# neopixel_studio_light.net
KiCad netlist of a schematic drawn in EAGLE
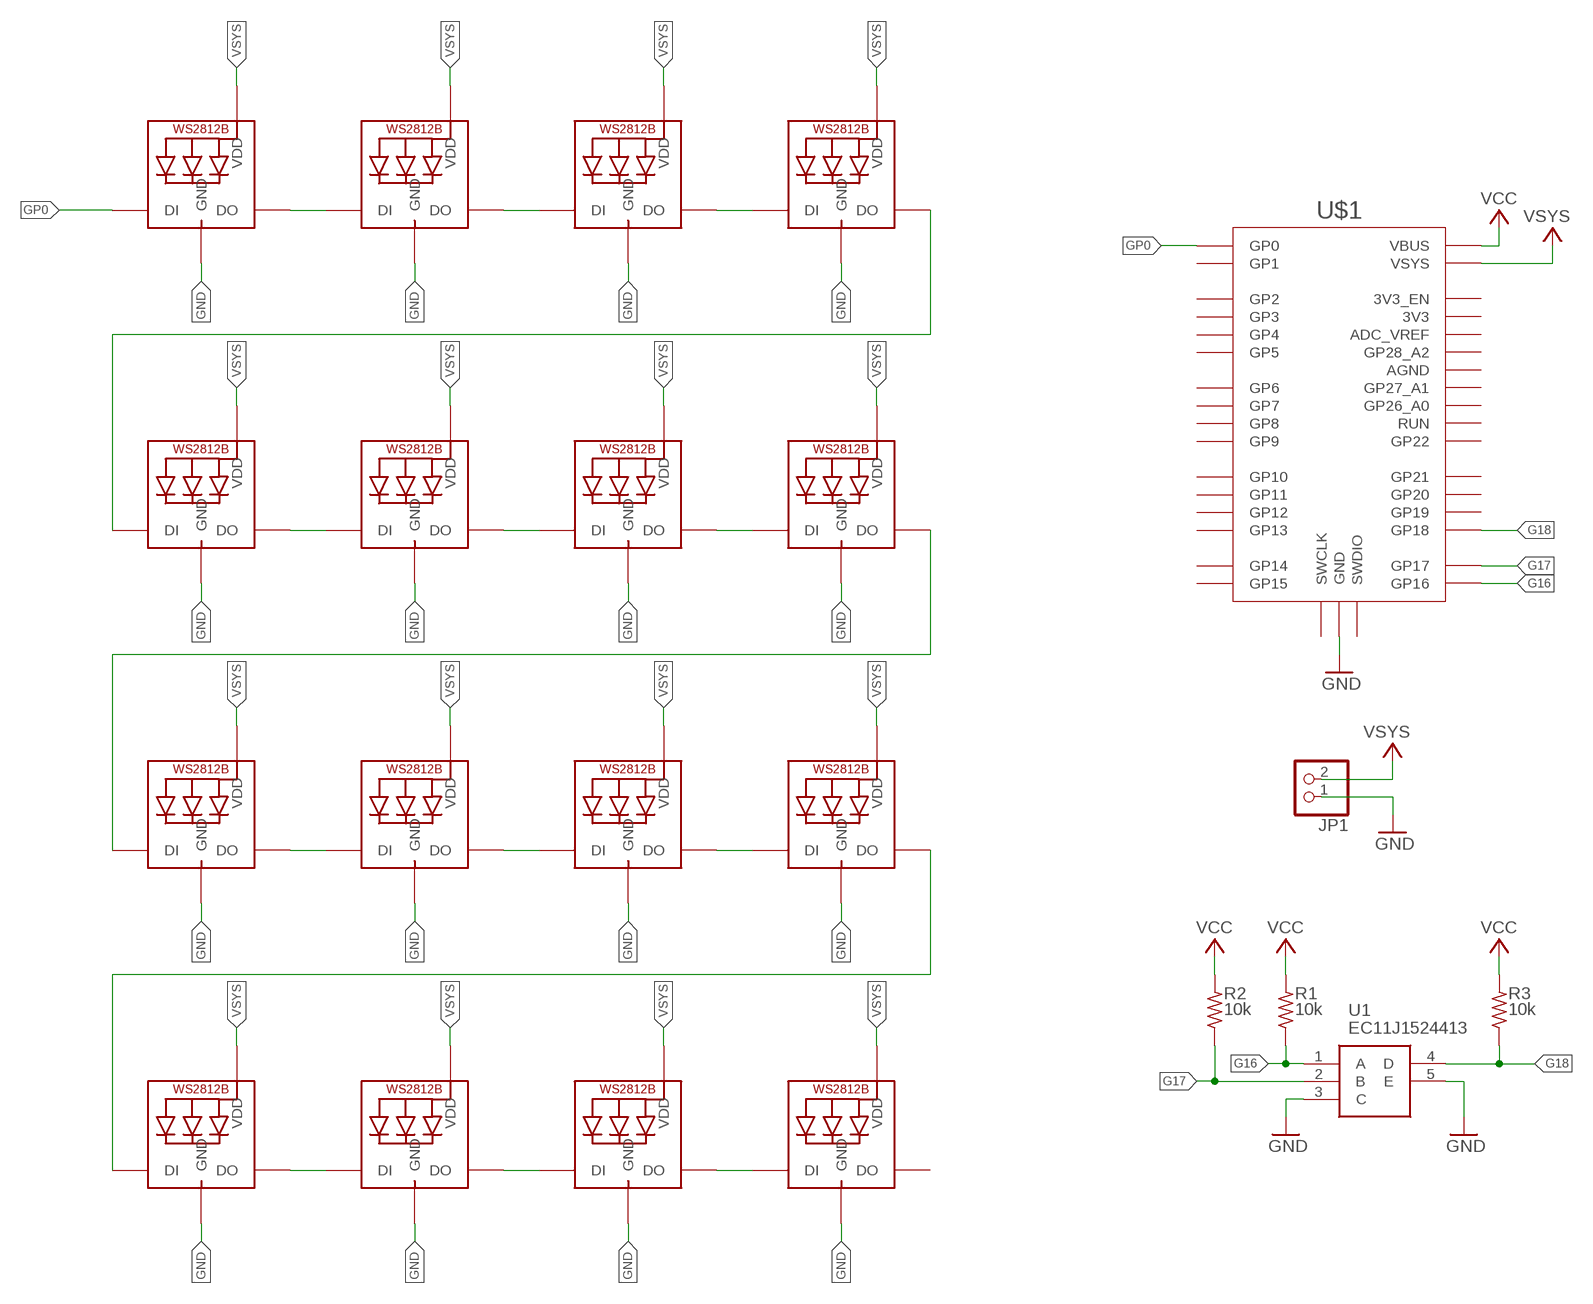
[diagram p0: schematic, sheet 1]

(export (version "E")
  (design (tool "Eeschema 10.0.6"))
  (components
    (comp (ref "JP1")
      (value "PINHD-1X2")
      (footprint "eagle-import:1X02")
      (libsource (lib "eagle-import") (part "PINHD-1X2"))
    )
    (comp (ref "LED1")
      (value "WS2812B5050")
      (footprint "eagle-import:WS2812B")
      (libsource (lib "eagle-import") (part "WS2812B5050"))
    )
    (comp (ref "LED2")
      (value "WS2812B5050")
      (footprint "eagle-import:WS2812B")
      (libsource (lib "eagle-import") (part "WS2812B5050"))
    )
    (comp (ref "LED3")
      (value "WS2812B5050")
      (footprint "eagle-import:WS2812B")
      (libsource (lib "eagle-import") (part "WS2812B5050"))
    )
    (comp (ref "LED4")
      (value "WS2812B5050")
      (footprint "eagle-import:WS2812B")
      (libsource (lib "eagle-import") (part "WS2812B5050"))
    )
    (comp (ref "LED5")
      (value "WS2812B5050")
      (footprint "eagle-import:WS2812B")
      (libsource (lib "eagle-import") (part "WS2812B5050"))
    )
    (comp (ref "LED6")
      (value "WS2812B5050")
      (footprint "eagle-import:WS2812B")
      (libsource (lib "eagle-import") (part "WS2812B5050"))
    )
    (comp (ref "LED7")
      (value "WS2812B5050")
      (footprint "eagle-import:WS2812B")
      (libsource (lib "eagle-import") (part "WS2812B5050"))
    )
    (comp (ref "LED8")
      (value "WS2812B5050")
      (footprint "eagle-import:WS2812B")
      (libsource (lib "eagle-import") (part "WS2812B5050"))
    )
    (comp (ref "LED9")
      (value "WS2812B5050")
      (footprint "eagle-import:WS2812B")
      (libsource (lib "eagle-import") (part "WS2812B5050"))
    )
    (comp (ref "LED10")
      (value "WS2812B5050")
      (footprint "eagle-import:WS2812B")
      (libsource (lib "eagle-import") (part "WS2812B5050"))
    )
    (comp (ref "LED11")
      (value "WS2812B5050")
      (footprint "eagle-import:WS2812B")
      (libsource (lib "eagle-import") (part "WS2812B5050"))
    )
    (comp (ref "LED12")
      (value "WS2812B5050")
      (footprint "eagle-import:WS2812B")
      (libsource (lib "eagle-import") (part "WS2812B5050"))
    )
    (comp (ref "LED13")
      (value "WS2812B5050")
      (footprint "eagle-import:WS2812B")
      (libsource (lib "eagle-import") (part "WS2812B5050"))
    )
    (comp (ref "LED14")
      (value "WS2812B5050")
      (footprint "eagle-import:WS2812B")
      (libsource (lib "eagle-import") (part "WS2812B5050"))
    )
    (comp (ref "LED15")
      (value "WS2812B5050")
      (footprint "eagle-import:WS2812B")
      (libsource (lib "eagle-import") (part "WS2812B5050"))
    )
    (comp (ref "LED16")
      (value "WS2812B5050")
      (footprint "eagle-import:WS2812B")
      (libsource (lib "eagle-import") (part "WS2812B5050"))
    )
    (comp (ref "R1")
      (value "10k")
      (footprint "eagle-import:R0603")
      (libsource (lib "eagle-import") (part "R-US_R0603"))
    )
    (comp (ref "R2")
      (value "10k")
      (footprint "eagle-import:R0603")
      (libsource (lib "eagle-import") (part "R-US_R0603"))
    )
    (comp (ref "R3")
      (value "10k")
      (footprint "eagle-import:R0603")
      (libsource (lib "eagle-import") (part "R-US_R0603"))
    )
    (comp (ref "U$1")
      (value "RPI_PICO-SMD")
      (footprint "eagle-import:RPI_PICO")
      (libsource (lib "eagle-import") (part "RPI_PICO-SMD"))
    )
    (comp (ref "U1")
      (value "EC11J1524413")
      (footprint "eagle-import:EC11J1524413")
      (libsource (lib "eagle-import") (part "EC11J1524413"))
    )
  )
  (nets
    (net (code "1") (name "G16") (class "Default")
      (node (ref "R1") (pin "1") (pinfunction "1_1") (pintype "passive"))
      (node (ref "U$1") (pin "GP16") (pinfunction "GP16_GP16") (pintype "bidirectional"))
      (node (ref "U1") (pin "1") (pinfunction "A_1") (pintype "bidirectional"))
    )
    (net (code "2") (name "G17") (class "Default")
      (node (ref "R2") (pin "1") (pinfunction "1_1") (pintype "passive"))
      (node (ref "U$1") (pin "GP17") (pinfunction "GP17_GP17") (pintype "bidirectional"))
      (node (ref "U1") (pin "2") (pinfunction "B_2") (pintype "bidirectional"))
    )
    (net (code "3") (name "G18") (class "Default")
      (node (ref "R3") (pin "1") (pinfunction "1_1") (pintype "passive"))
      (node (ref "U$1") (pin "GP18") (pinfunction "GP18_GP18") (pintype "bidirectional"))
      (node (ref "U1") (pin "4") (pinfunction "D_4") (pintype "bidirectional"))
    )
    (net (code "4") (name "GND") (class "Default")
      (node (ref "JP1") (pin "1") (pinfunction "1_1") (pintype "passive"))
      (node (ref "LED1") (pin "3-GND") (pinfunction "GND_3-GND") (pintype "power_in"))
      (node (ref "LED10") (pin "3-GND") (pinfunction "GND_3-GND") (pintype "power_in"))
      (node (ref "LED11") (pin "3-GND") (pinfunction "GND_3-GND") (pintype "power_in"))
      (node (ref "LED12") (pin "3-GND") (pinfunction "GND_3-GND") (pintype "power_in"))
      (node (ref "LED13") (pin "3-GND") (pinfunction "GND_3-GND") (pintype "power_in"))
      (node (ref "LED14") (pin "3-GND") (pinfunction "GND_3-GND") (pintype "power_in"))
      (node (ref "LED15") (pin "3-GND") (pinfunction "GND_3-GND") (pintype "power_in"))
      (node (ref "LED16") (pin "3-GND") (pinfunction "GND_3-GND") (pintype "power_in"))
      (node (ref "LED2") (pin "3-GND") (pinfunction "GND_3-GND") (pintype "power_in"))
      (node (ref "LED3") (pin "3-GND") (pinfunction "GND_3-GND") (pintype "power_in"))
      (node (ref "LED4") (pin "3-GND") (pinfunction "GND_3-GND") (pintype "power_in"))
      (node (ref "LED5") (pin "3-GND") (pinfunction "GND_3-GND") (pintype "power_in"))
      (node (ref "LED6") (pin "3-GND") (pinfunction "GND_3-GND") (pintype "power_in"))
      (node (ref "LED7") (pin "3-GND") (pinfunction "GND_3-GND") (pintype "power_in"))
      (node (ref "LED8") (pin "3-GND") (pinfunction "GND_3-GND") (pintype "power_in"))
      (node (ref "LED9") (pin "3-GND") (pinfunction "GND_3-GND") (pintype "power_in"))
      (node (ref "U$1") (pin "GND@1") (pinfunction "GND_GND@1") (pintype "bidirectional"))
      (node (ref "U$1") (pin "GND@2") (pinfunction "GND_GND@2") (pintype "bidirectional"))
      (node (ref "U$1") (pin "GND@3") (pinfunction "GND_GND@3") (pintype "bidirectional"))
      (node (ref "U$1") (pin "GND@4") (pinfunction "GND_GND@4") (pintype "bidirectional"))
      (node (ref "U$1") (pin "GND@5") (pinfunction "GND_GND@5") (pintype "bidirectional"))
      (node (ref "U$1") (pin "GND@6") (pinfunction "GND_GND@6") (pintype "bidirectional"))
      (node (ref "U$1") (pin "GND@7") (pinfunction "GND_GND@7") (pintype "bidirectional"))
      (node (ref "U$1") (pin "GND@8") (pinfunction "GND_GND@8") (pintype "bidirectional"))
      (node (ref "U1") (pin "3") (pinfunction "C_3") (pintype "bidirectional"))
      (node (ref "U1") (pin "5") (pinfunction "E_5") (pintype "bidirectional"))
    )
    (net (code "5") (name "GP0") (class "Default")
      (node (ref "LED1") (pin "4-DIN") (pinfunction "DI_4-DIN") (pintype "input"))
      (node (ref "U$1") (pin "GP0") (pinfunction "GP0_GP0") (pintype "bidirectional"))
    )
    (net (code "6") (name "Net-(LED1-DO)") (class "Default")
      (node (ref "LED1") (pin "2-DOUT") (pinfunction "DO_2-DOUT") (pintype "output"))
      (node (ref "LED2") (pin "4-DIN") (pinfunction "DI_4-DIN") (pintype "input"))
    )
    (net (code "7") (name "Net-(LED2-DO)") (class "Default")
      (node (ref "LED2") (pin "2-DOUT") (pinfunction "DO_2-DOUT") (pintype "output"))
      (node (ref "LED3") (pin "4-DIN") (pinfunction "DI_4-DIN") (pintype "input"))
    )
    (net (code "8") (name "Net-(LED3-DO)") (class "Default")
      (node (ref "LED3") (pin "2-DOUT") (pinfunction "DO_2-DOUT") (pintype "output"))
      (node (ref "LED4") (pin "4-DIN") (pinfunction "DI_4-DIN") (pintype "input"))
    )
    (net (code "9") (name "Net-(LED4-DO)") (class "Default")
      (node (ref "LED4") (pin "2-DOUT") (pinfunction "DO_2-DOUT") (pintype "output"))
      (node (ref "LED5") (pin "4-DIN") (pinfunction "DI_4-DIN") (pintype "input"))
    )
    (net (code "10") (name "Net-(LED5-DO)") (class "Default")
      (node (ref "LED5") (pin "2-DOUT") (pinfunction "DO_2-DOUT") (pintype "output"))
      (node (ref "LED6") (pin "4-DIN") (pinfunction "DI_4-DIN") (pintype "input"))
    )
    (net (code "11") (name "Net-(LED6-DO)") (class "Default")
      (node (ref "LED6") (pin "2-DOUT") (pinfunction "DO_2-DOUT") (pintype "output"))
      (node (ref "LED7") (pin "4-DIN") (pinfunction "DI_4-DIN") (pintype "input"))
    )
    (net (code "12") (name "Net-(LED7-DO)") (class "Default")
      (node (ref "LED7") (pin "2-DOUT") (pinfunction "DO_2-DOUT") (pintype "output"))
      (node (ref "LED8") (pin "4-DIN") (pinfunction "DI_4-DIN") (pintype "input"))
    )
    (net (code "13") (name "Net-(LED8-DO)") (class "Default")
      (node (ref "LED8") (pin "2-DOUT") (pinfunction "DO_2-DOUT") (pintype "output"))
      (node (ref "LED9") (pin "4-DIN") (pinfunction "DI_4-DIN") (pintype "input"))
    )
    (net (code "14") (name "Net-(LED10-DI)") (class "Default")
      (node (ref "LED10") (pin "4-DIN") (pinfunction "DI_4-DIN") (pintype "input"))
      (node (ref "LED9") (pin "2-DOUT") (pinfunction "DO_2-DOUT") (pintype "output"))
    )
    (net (code "15") (name "Net-(LED10-DO)") (class "Default")
      (node (ref "LED10") (pin "2-DOUT") (pinfunction "DO_2-DOUT") (pintype "output"))
      (node (ref "LED11") (pin "4-DIN") (pinfunction "DI_4-DIN") (pintype "input"))
    )
    (net (code "16") (name "Net-(LED11-DO)") (class "Default")
      (node (ref "LED11") (pin "2-DOUT") (pinfunction "DO_2-DOUT") (pintype "output"))
      (node (ref "LED12") (pin "4-DIN") (pinfunction "DI_4-DIN") (pintype "input"))
    )
    (net (code "17") (name "Net-(LED12-DO)") (class "Default")
      (node (ref "LED12") (pin "2-DOUT") (pinfunction "DO_2-DOUT") (pintype "output"))
      (node (ref "LED13") (pin "4-DIN") (pinfunction "DI_4-DIN") (pintype "input"))
    )
    (net (code "18") (name "Net-(LED13-DO)") (class "Default")
      (node (ref "LED13") (pin "2-DOUT") (pinfunction "DO_2-DOUT") (pintype "output"))
      (node (ref "LED14") (pin "4-DIN") (pinfunction "DI_4-DIN") (pintype "input"))
    )
    (net (code "19") (name "Net-(LED14-DO)") (class "Default")
      (node (ref "LED14") (pin "2-DOUT") (pinfunction "DO_2-DOUT") (pintype "output"))
      (node (ref "LED15") (pin "4-DIN") (pinfunction "DI_4-DIN") (pintype "input"))
    )
    (net (code "20") (name "Net-(LED15-DO)") (class "Default")
      (node (ref "LED15") (pin "2-DOUT") (pinfunction "DO_2-DOUT") (pintype "output"))
      (node (ref "LED16") (pin "4-DIN") (pinfunction "DI_4-DIN") (pintype "input"))
    )
    (net (code "21") (name "VCC") (class "Default")
      (node (ref "R1") (pin "2") (pinfunction "2_2") (pintype "passive"))
      (node (ref "R2") (pin "2") (pinfunction "2_2") (pintype "passive"))
      (node (ref "R3") (pin "2") (pinfunction "2_2") (pintype "passive"))
      (node (ref "U$1") (pin "VBUS") (pinfunction "VBUS_VBUS") (pintype "bidirectional"))
    )
    (net (code "22") (name "VSYS") (class "Default")
      (node (ref "JP1") (pin "2") (pinfunction "2_2") (pintype "passive"))
      (node (ref "LED1") (pin "1-VDD") (pinfunction "VDD_1-VDD") (pintype "power_in"))
      (node (ref "LED10") (pin "1-VDD") (pinfunction "VDD_1-VDD") (pintype "power_in"))
      (node (ref "LED11") (pin "1-VDD") (pinfunction "VDD_1-VDD") (pintype "power_in"))
      (node (ref "LED12") (pin "1-VDD") (pinfunction "VDD_1-VDD") (pintype "power_in"))
      (node (ref "LED13") (pin "1-VDD") (pinfunction "VDD_1-VDD") (pintype "power_in"))
      (node (ref "LED14") (pin "1-VDD") (pinfunction "VDD_1-VDD") (pintype "power_in"))
      (node (ref "LED15") (pin "1-VDD") (pinfunction "VDD_1-VDD") (pintype "power_in"))
      (node (ref "LED16") (pin "1-VDD") (pinfunction "VDD_1-VDD") (pintype "power_in"))
      (node (ref "LED2") (pin "1-VDD") (pinfunction "VDD_1-VDD") (pintype "power_in"))
      (node (ref "LED3") (pin "1-VDD") (pinfunction "VDD_1-VDD") (pintype "power_in"))
      (node (ref "LED4") (pin "1-VDD") (pinfunction "VDD_1-VDD") (pintype "power_in"))
      (node (ref "LED5") (pin "1-VDD") (pinfunction "VDD_1-VDD") (pintype "power_in"))
      (node (ref "LED6") (pin "1-VDD") (pinfunction "VDD_1-VDD") (pintype "power_in"))
      (node (ref "LED7") (pin "1-VDD") (pinfunction "VDD_1-VDD") (pintype "power_in"))
      (node (ref "LED8") (pin "1-VDD") (pinfunction "VDD_1-VDD") (pintype "power_in"))
      (node (ref "LED9") (pin "1-VDD") (pinfunction "VDD_1-VDD") (pintype "power_in"))
      (node (ref "U$1") (pin "VSYS") (pinfunction "VSYS_VSYS") (pintype "bidirectional"))
    )
    (net (code "23") (name "unconnected-(LED16-DO-Pad2-DOUT)") (class "Default")
      (node (ref "LED16") (pin "2-DOUT") (pinfunction "DO_2-DOUT") (pintype "output"))
    )
    (net (code "24") (name "unconnected-(U$1-Pad3V3)") (class "Default")
      (node (ref "U$1") (pin "3V3") (pinfunction "3V3_3V3") (pintype "bidirectional"))
    )
    (net (code "25") (name "unconnected-(U$1-Pad3V3_EN)") (class "Default")
      (node (ref "U$1") (pin "3V3_EN") (pinfunction "3V3_EN_3V3_EN") (pintype "bidirectional"))
    )
    (net (code "26") (name "unconnected-(U$1-PadADC_VREF)") (class "Default")
      (node (ref "U$1") (pin "ADC_VREF") (pinfunction "ADC_VREF_ADC_VREF") (pintype "bidirectional"))
    )
    (net (code "27") (name "unconnected-(U$1-PadAGND)") (class "Default")
      (node (ref "U$1") (pin "AGND") (pinfunction "AGND_AGND") (pintype "bidirectional"))
    )
    (net (code "28") (name "unconnected-(U$1-PadGP1)") (class "Default")
      (node (ref "U$1") (pin "GP1") (pinfunction "GP1_GP1") (pintype "bidirectional"))
    )
    (net (code "29") (name "unconnected-(U$1-PadGP2)") (class "Default")
      (node (ref "U$1") (pin "GP2") (pinfunction "GP2_GP2") (pintype "bidirectional"))
    )
    (net (code "30") (name "unconnected-(U$1-PadGP3)") (class "Default")
      (node (ref "U$1") (pin "GP3") (pinfunction "GP3_GP3") (pintype "bidirectional"))
    )
    (net (code "31") (name "unconnected-(U$1-PadGP4)") (class "Default")
      (node (ref "U$1") (pin "GP4") (pinfunction "GP4_GP4") (pintype "bidirectional"))
    )
    (net (code "32") (name "unconnected-(U$1-PadGP5)") (class "Default")
      (node (ref "U$1") (pin "GP5") (pinfunction "GP5_GP5") (pintype "bidirectional"))
    )
    (net (code "33") (name "unconnected-(U$1-PadGP6)") (class "Default")
      (node (ref "U$1") (pin "GP6") (pinfunction "GP6_GP6") (pintype "bidirectional"))
    )
    (net (code "34") (name "unconnected-(U$1-PadGP7)") (class "Default")
      (node (ref "U$1") (pin "GP7") (pinfunction "GP7_GP7") (pintype "bidirectional"))
    )
    (net (code "35") (name "unconnected-(U$1-PadGP8)") (class "Default")
      (node (ref "U$1") (pin "GP8") (pinfunction "GP8_GP8") (pintype "bidirectional"))
    )
    (net (code "36") (name "unconnected-(U$1-PadGP9)") (class "Default")
      (node (ref "U$1") (pin "GP9") (pinfunction "GP9_GP9") (pintype "bidirectional"))
    )
    (net (code "37") (name "unconnected-(U$1-PadGP10)") (class "Default")
      (node (ref "U$1") (pin "GP10") (pinfunction "GP10_GP10") (pintype "bidirectional"))
    )
    (net (code "38") (name "unconnected-(U$1-PadGP11)") (class "Default")
      (node (ref "U$1") (pin "GP11") (pinfunction "GP11_GP11") (pintype "bidirectional"))
    )
    (net (code "39") (name "unconnected-(U$1-PadGP12)") (class "Default")
      (node (ref "U$1") (pin "GP12") (pinfunction "GP12_GP12") (pintype "bidirectional"))
    )
    (net (code "40") (name "unconnected-(U$1-PadGP13)") (class "Default")
      (node (ref "U$1") (pin "GP13") (pinfunction "GP13_GP13") (pintype "bidirectional"))
    )
    (net (code "41") (name "unconnected-(U$1-PadGP14)") (class "Default")
      (node (ref "U$1") (pin "GP14") (pinfunction "GP14_GP14") (pintype "bidirectional"))
    )
    (net (code "42") (name "unconnected-(U$1-PadGP15)") (class "Default")
      (node (ref "U$1") (pin "GP15") (pinfunction "GP15_GP15") (pintype "bidirectional"))
    )
    (net (code "43") (name "unconnected-(U$1-PadGP19)") (class "Default")
      (node (ref "U$1") (pin "GP19") (pinfunction "GP19_GP19") (pintype "bidirectional"))
    )
    (net (code "44") (name "unconnected-(U$1-PadGP20)") (class "Default")
      (node (ref "U$1") (pin "GP20") (pinfunction "GP20_GP20") (pintype "bidirectional"))
    )
    (net (code "45") (name "unconnected-(U$1-PadGP21)") (class "Default")
      (node (ref "U$1") (pin "GP21") (pinfunction "GP21_GP21") (pintype "bidirectional"))
    )
    (net (code "46") (name "unconnected-(U$1-PadGP22)") (class "Default")
      (node (ref "U$1") (pin "GP22") (pinfunction "GP22_GP22") (pintype "bidirectional"))
    )
    (net (code "47") (name "unconnected-(U$1-PadGP26_A0)") (class "Default")
      (node (ref "U$1") (pin "GP26_A0") (pinfunction "GP26_A0_GP26_A0") (pintype "bidirectional"))
    )
    (net (code "48") (name "unconnected-(U$1-PadGP27_A1)") (class "Default")
      (node (ref "U$1") (pin "GP27_A1") (pinfunction "GP27_A1_GP27_A1") (pintype "bidirectional"))
    )
    (net (code "49") (name "unconnected-(U$1-PadGP28_A2)") (class "Default")
      (node (ref "U$1") (pin "GP28_A2") (pinfunction "GP28_A2_GP28_A2") (pintype "bidirectional"))
    )
    (net (code "50") (name "unconnected-(U$1-PadRUN)") (class "Default")
      (node (ref "U$1") (pin "RUN") (pinfunction "RUN_RUN") (pintype "bidirectional"))
    )
    (net (code "51") (name "unconnected-(U$1-PadSWCLK)") (class "Default")
      (node (ref "U$1") (pin "SWCLK") (pinfunction "SWCLK_SWCLK") (pintype "bidirectional"))
    )
    (net (code "52") (name "unconnected-(U$1-PadSWDIO)") (class "Default")
      (node (ref "U$1") (pin "SWDIO") (pinfunction "SWDIO_SWDIO") (pintype "bidirectional"))
    )
  )
)
